# PLL1.net
KiCad netlist of a schematic drawn in Altium Designer
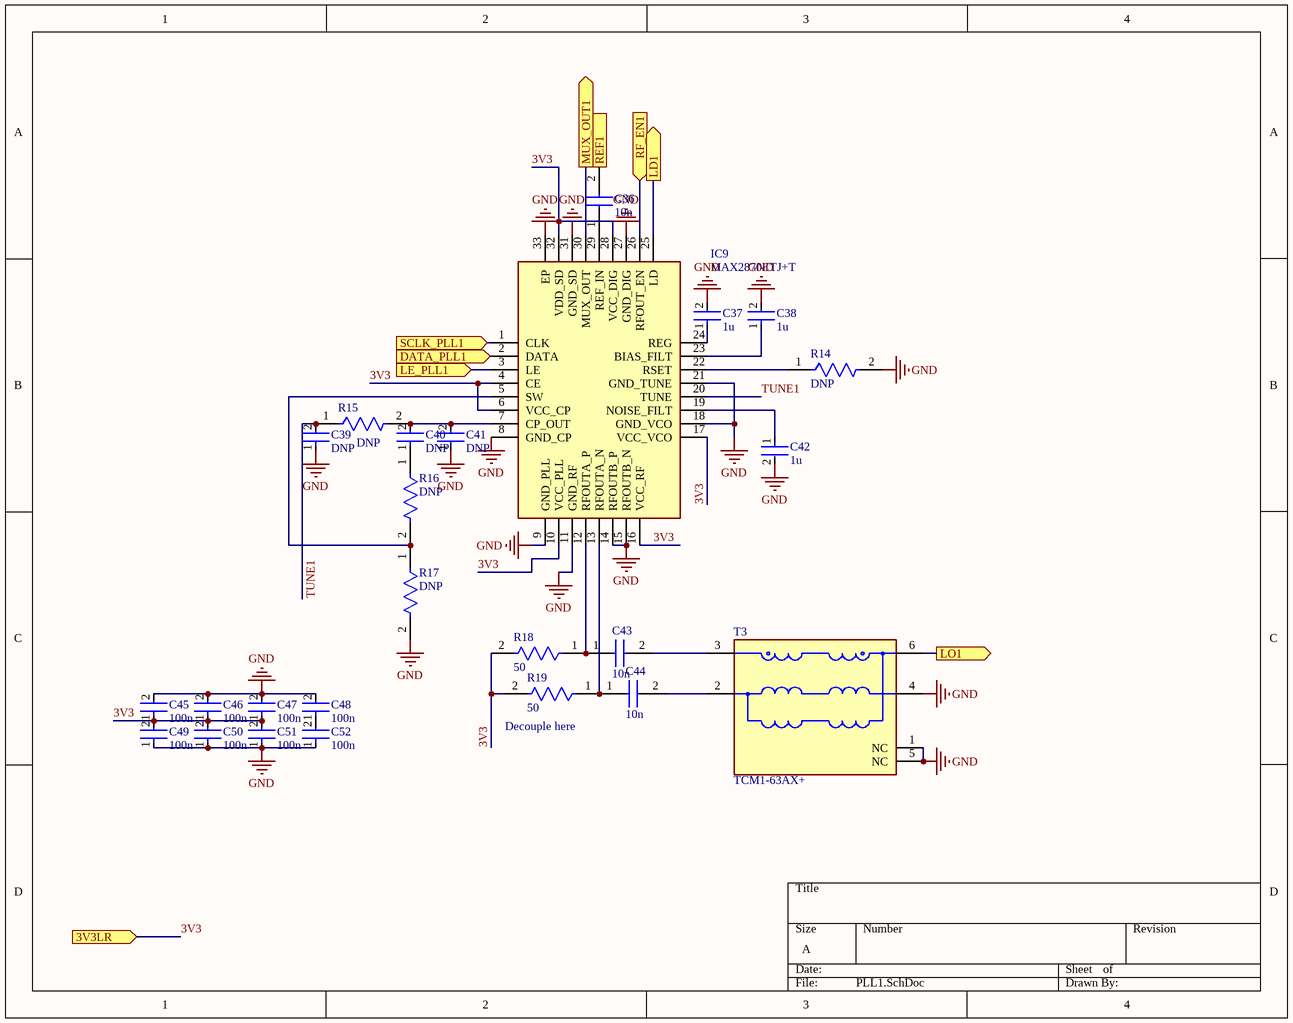
[diagram p0: PLL1.SchDoc]

(export (version "E")
  (design (tool "Eeschema 10.0.6"))
  (components
    (comp (ref "C36")
      (value "10n")
      (footprint "SamacSys:CAPC1005X61N")
      (description "Capacitor")
      (fields
        (field (name "MANUFACTURER_PART_NUMBER") "520L103KT16T")
        (field (name "MOUSER PART NUMBER") "581-520L103KT16T")
      )
      (libsource (lib "*") (part "520L103KT16T"))
    )
    (comp (ref "C37")
      (value "1u")
      (footprint "FP-GRM155-0_1-MFG")
      (description "Chip Multilayer Ceramic Capacitors for General Purpose, 0402, 1.0uF, X5R, 15%, 10%, 50V")
      (libsource (lib "Altium Content Vault") (part "11868f565c42a9108669ba33697ecf6"))
    )
    (comp (ref "C38")
      (value "1u")
      (footprint "FP-GRM155-0_1-MFG")
      (description "Chip Multilayer Ceramic Capacitors for General Purpose, 0402, 1.0uF, X5R, 15%, 10%, 50V")
      (libsource (lib "Altium Content Vault") (part "11868f565c42a9108669ba33697ecf6"))
    )
    (comp (ref "C39")
      (value "DNP")
      (footprint "FP-GRM155-0_05-IPC_C")
      (description "Chip Multilayer Ceramic Capacitors for General Purpose, 0402, 0.10uF, X5R, 15%, 10%, 100V")
      (fields (field (name "TOLERANCE") "10%"))
      (libsource (lib "Altium Content Vault") (part "02cd4be3c70576c341d710602a673aa"))
    )
    (comp (ref "C40")
      (value "DNP")
      (footprint "FP-GRM155-0_05-IPC_C")
      (description "Chip Multilayer Ceramic Capacitors for General Purpose, 0402, 0.10uF, X5R, 15%, 10%, 100V")
      (fields (field (name "TOLERANCE") "10%"))
      (libsource (lib "Altium Content Vault") (part "02cd4be3c70576c341d710602a673aa"))
    )
    (comp (ref "C41")
      (value "DNP")
      (footprint "FP-GRM155-0_05-IPC_C")
      (description "Chip Multilayer Ceramic Capacitors for General Purpose, 0402, 0.10uF, X5R, 15%, 10%, 100V")
      (fields (field (name "TOLERANCE") "10%"))
      (libsource (lib "Altium Content Vault") (part "02cd4be3c70576c341d710602a673aa"))
    )
    (comp (ref "C42")
      (value "1u")
      (footprint "FP-GRM155-0_1-MFG")
      (description "Chip Multilayer Ceramic Capacitors for General Purpose, 0402, 1.0uF, X5R, 15%, 10%, 50V")
      (libsource (lib "Altium Content Vault") (part "11868f565c42a9108669ba33697ecf6"))
    )
    (comp (ref "C43")
      (value "10n")
      (footprint "SamacSys:CAPC1005X61N")
      (description "Capacitor")
      (fields
        (field (name "MANUFACTURER_PART_NUMBER") "520L103KT16T")
        (field (name "MOUSER PART NUMBER") "581-520L103KT16T")
      )
      (libsource (lib "*") (part "520L103KT16T"))
    )
    (comp (ref "C44")
      (value "10n")
      (footprint "SamacSys:CAPC1005X61N")
      (description "Capacitor")
      (fields
        (field (name "MANUFACTURER_PART_NUMBER") "520L103KT16T")
        (field (name "MOUSER PART NUMBER") "581-520L103KT16T")
      )
      (libsource (lib "*") (part "520L103KT16T"))
    )
    (comp (ref "C45")
      (value "100n")
      (footprint "FP-GRM155-0_05-IPC_C")
      (description "Chip Multilayer Ceramic Capacitors for General Purpose, 0402, 0.10uF, X5R, 15%, 10%, 100V")
      (fields (field (name "TOLERANCE") "10%"))
      (libsource (lib "Altium Content Vault") (part "02cd4be3c70576c341d710602a673aa"))
    )
    (comp (ref "C46")
      (value "100n")
      (footprint "FP-GRM155-0_05-IPC_C")
      (description "Chip Multilayer Ceramic Capacitors for General Purpose, 0402, 0.10uF, X5R, 15%, 10%, 100V")
      (fields (field (name "TOLERANCE") "10%"))
      (libsource (lib "Altium Content Vault") (part "02cd4be3c70576c341d710602a673aa"))
    )
    (comp (ref "C47")
      (value "100n")
      (footprint "FP-GRM155-0_05-IPC_C")
      (description "Chip Multilayer Ceramic Capacitors for General Purpose, 0402, 0.10uF, X5R, 15%, 10%, 100V")
      (fields (field (name "TOLERANCE") "10%"))
      (libsource (lib "Altium Content Vault") (part "02cd4be3c70576c341d710602a673aa"))
    )
    (comp (ref "C48")
      (value "100n")
      (footprint "FP-GRM155-0_05-IPC_C")
      (description "Chip Multilayer Ceramic Capacitors for General Purpose, 0402, 0.10uF, X5R, 15%, 10%, 100V")
      (fields (field (name "TOLERANCE") "10%"))
      (libsource (lib "Altium Content Vault") (part "02cd4be3c70576c341d710602a673aa"))
    )
    (comp (ref "C49")
      (value "100n")
      (footprint "FP-GRM155-0_05-IPC_C")
      (description "Chip Multilayer Ceramic Capacitors for General Purpose, 0402, 0.10uF, X5R, 15%, 10%, 100V")
      (fields (field (name "TOLERANCE") "10%"))
      (libsource (lib "Altium Content Vault") (part "02cd4be3c70576c341d710602a673aa"))
    )
    (comp (ref "C50")
      (value "100n")
      (footprint "FP-GRM155-0_05-IPC_C")
      (description "Chip Multilayer Ceramic Capacitors for General Purpose, 0402, 0.10uF, X5R, 15%, 10%, 100V")
      (fields (field (name "TOLERANCE") "10%"))
      (libsource (lib "Altium Content Vault") (part "02cd4be3c70576c341d710602a673aa"))
    )
    (comp (ref "C51")
      (value "100n")
      (footprint "FP-GRM155-0_05-IPC_C")
      (description "Chip Multilayer Ceramic Capacitors for General Purpose, 0402, 0.10uF, X5R, 15%, 10%, 100V")
      (fields (field (name "TOLERANCE") "10%"))
      (libsource (lib "Altium Content Vault") (part "02cd4be3c70576c341d710602a673aa"))
    )
    (comp (ref "C52")
      (value "100n")
      (footprint "FP-GRM155-0_05-IPC_C")
      (description "Chip Multilayer Ceramic Capacitors for General Purpose, 0402, 0.10uF, X5R, 15%, 10%, 100V")
      (fields (field (name "TOLERANCE") "10%"))
      (libsource (lib "Altium Content Vault") (part "02cd4be3c70576c341d710602a673aa"))
    )
    (comp (ref "IC9")
      (value "MAX2870ETJ+T")
      (footprint "SamacSys:QFN50P500X500X80-33N")
      (description "Integrated Circuit")
      (fields (field (name "MOUSER PART NUMBER") "700-MAX2870ETJ+T"))
      (libsource (lib "*") (part "MAX2870ETJ+T"))
    )
    (comp (ref "R14")
      (value "DNP")
      (footprint "FP-AC0402-IPC_B")
      (description "RES 13.3kΩ ±1% 0.063W 0402")
      (fields (field (name "TOLERANCE") "1%"))
      (libsource (lib "Altium Content Vault") (part "1029c3af85768c4190bb7ad29bc67b5"))
    )
    (comp (ref "R15")
      (value "DNP")
      (footprint "FP-AC0402-IPC_B")
      (description "RES 13.3kΩ ±1% 0.063W 0402")
      (fields (field (name "TOLERANCE") "1%"))
      (libsource (lib "Altium Content Vault") (part "1029c3af85768c4190bb7ad29bc67b5"))
    )
    (comp (ref "R16")
      (value "DNP")
      (footprint "FP-AC0402-IPC_B")
      (description "RES 13.3kΩ ±1% 0.063W 0402")
      (fields (field (name "TOLERANCE") "1%"))
      (libsource (lib "Altium Content Vault") (part "1029c3af85768c4190bb7ad29bc67b5"))
    )
    (comp (ref "R17")
      (value "DNP")
      (footprint "FP-AC0402-IPC_B")
      (description "RES 13.3kΩ ±1% 0.063W 0402")
      (fields (field (name "TOLERANCE") "1%"))
      (libsource (lib "Altium Content Vault") (part "1029c3af85768c4190bb7ad29bc67b5"))
    )
    (comp (ref "R18")
      (value "50")
      (footprint "FP-RC0402-0_4-MFG")
      (fields (field (name "TOLERANCE") "5%"))
      (libsource (lib "Altium Content Vault") (part "1029c3af85768c4190bb7ad29bc67b5"))
    )
    (comp (ref "R19")
      (value "50")
      (footprint "FP-RC0402-0_4-MFG")
      (fields (field (name "TOLERANCE") "5%"))
      (libsource (lib "Altium Content Vault") (part "1029c3af85768c4190bb7ad29bc67b5"))
    )
    (comp (ref "T3")
      (value "TCM1-63AX+")
      (footprint "FP-TCM1-63AX+-MFG")
      (description "1:1 CORE & WIRE Transformer, 10 - 6000 MHz, 50Ω")
      (fields
        (field (name "MANUFACTURER") "Mini-Circuits")
        (field (name "OCTOPART") "https://octopart.com/tcm1-63ax%2B-mini-circuits-107315723")
      )
      (libsource (lib "Altium Content Vault") (part "572340aedd709dbafee1a1d3331a406"))
    )
  )
  (nets
    (net (code "1") (name "/3V3") (class "Default")
      (node (ref "C45") (pin "1") (pinfunction "1_1") (pintype "passive"))
      (node (ref "C46") (pin "1") (pinfunction "1_1") (pintype "passive"))
      (node (ref "C47") (pin "1") (pinfunction "1_1") (pintype "passive"))
      (node (ref "C49") (pin "2") (pinfunction "2_2") (pintype "passive"))
      (node (ref "C50") (pin "2") (pinfunction "2_2") (pintype "passive"))
      (node (ref "C51") (pin "2") (pinfunction "2_2") (pintype "passive"))
      (node (ref "IC9") (pin "10") (pinfunction "VCC_PLL_10") (pintype "passive"))
      (node (ref "IC9") (pin "16") (pinfunction "VCC_RF_16") (pintype "passive"))
      (node (ref "IC9") (pin "17") (pinfunction "VCC_VCO_17") (pintype "passive"))
      (node (ref "IC9") (pin "28") (pinfunction "VCC_DIG_28") (pintype "passive"))
      (node (ref "IC9") (pin "32") (pinfunction "VDD_SD_32") (pintype "passive"))
      (node (ref "IC9") (pin "4") (pinfunction "CE_4") (pintype "passive"))
      (node (ref "IC9") (pin "6") (pinfunction "VCC_CP_6") (pintype "passive"))
      (node (ref "R18") (pin "2") (pinfunction "2_2") (pintype "passive"))
      (node (ref "R19") (pin "2") (pinfunction "2_2") (pintype "passive"))
    )
    (net (code "2") (name "/DATA_PLL1") (class "Default")
      (node (ref "IC9") (pin "2") (pinfunction "DATA_2") (pintype "passive"))
    )
    (net (code "3") (name "/LD1") (class "Default")
      (node (ref "IC9") (pin "25") (pinfunction "LD_25") (pintype "passive"))
    )
    (net (code "4") (name "/LE_PLL1") (class "Default")
      (node (ref "IC9") (pin "3") (pinfunction "LE_3") (pintype "passive"))
    )
    (net (code "5") (name "/LO1") (class "Default")
      (node (ref "T3") (pin "6") (pinfunction "SECONDARY_DOT_6") (pintype "passive"))
    )
    (net (code "6") (name "/MUX_OUT1") (class "Default")
      (node (ref "IC9") (pin "30") (pinfunction "MUX_OUT_30") (pintype "passive"))
    )
    (net (code "7") (name "/REF1") (class "Default")
      (node (ref "C36") (pin "2") (pinfunction "2_2") (pintype "passive"))
    )
    (net (code "8") (name "/RF_EN1") (class "Default")
      (node (ref "IC9") (pin "26") (pinfunction "RFOUT_EN_26") (pintype "passive"))
    )
    (net (code "9") (name "/SCLK_PLL1") (class "Default")
      (node (ref "IC9") (pin "1") (pinfunction "CLK_1") (pintype "passive"))
    )
    (net (code "10") (name "/TUNE1") (class "Default")
      (node (ref "C39") (pin "2") (pinfunction "2_2") (pintype "passive"))
      (node (ref "IC9") (pin "20") (pinfunction "TUNE_20") (pintype "passive"))
      (node (ref "R15") (pin "1") (pinfunction "1_1") (pintype "passive"))
    )
    (net (code "11") (name "GND") (class "Default")
      (node (ref "C37") (pin "2") (pinfunction "2_2") (pintype "passive"))
      (node (ref "C38") (pin "2") (pinfunction "2_2") (pintype "passive"))
      (node (ref "C39") (pin "1") (pinfunction "1_1") (pintype "passive"))
      (node (ref "C41") (pin "1") (pinfunction "1_1") (pintype "passive"))
      (node (ref "C42") (pin "2") (pinfunction "2_2") (pintype "passive"))
      (node (ref "C45") (pin "2") (pinfunction "2_2") (pintype "passive"))
      (node (ref "C46") (pin "2") (pinfunction "2_2") (pintype "passive"))
      (node (ref "C47") (pin "2") (pinfunction "2_2") (pintype "passive"))
      (node (ref "C48") (pin "2") (pinfunction "2_2") (pintype "passive"))
      (node (ref "C49") (pin "1") (pinfunction "1_1") (pintype "passive"))
      (node (ref "C50") (pin "1") (pinfunction "1_1") (pintype "passive"))
      (node (ref "C51") (pin "1") (pinfunction "1_1") (pintype "passive"))
      (node (ref "C52") (pin "1") (pinfunction "1_1") (pintype "passive"))
      (node (ref "IC9") (pin "11") (pinfunction "GND_RF_11") (pintype "passive"))
      (node (ref "IC9") (pin "14") (pinfunction "RFOUTB_P_14") (pintype "passive"))
      (node (ref "IC9") (pin "15") (pinfunction "RFOUTB_N_15") (pintype "passive"))
      (node (ref "IC9") (pin "18") (pinfunction "GND_VCO_18") (pintype "passive"))
      (node (ref "IC9") (pin "21") (pinfunction "GND_TUNE_21") (pintype "passive"))
      (node (ref "IC9") (pin "27") (pinfunction "GND_DIG_27") (pintype "passive"))
      (node (ref "IC9") (pin "31") (pinfunction "GND_SD_31") (pintype "passive"))
      (node (ref "IC9") (pin "33") (pinfunction "EP_33") (pintype "passive"))
      (node (ref "IC9") (pin "8") (pinfunction "GND_CP_8") (pintype "passive"))
      (node (ref "IC9") (pin "9") (pinfunction "GND_PLL_9") (pintype "passive"))
      (node (ref "R14") (pin "2") (pinfunction "2_2") (pintype "passive"))
      (node (ref "R17") (pin "2") (pinfunction "2_2") (pintype "passive"))
      (node (ref "T3") (pin "1") (pinfunction "NC_1") (pintype "passive"))
      (node (ref "T3") (pin "4") (pinfunction "SECONDARY_4") (pintype "passive"))
      (node (ref "T3") (pin "5") (pinfunction "NC_5") (pintype "passive"))
    )
    (net (code "12") (name "Net-(C40-Pad1)") (class "Default")
      (node (ref "C40") (pin "1") (pinfunction "1_1") (pintype "passive"))
      (node (ref "R16") (pin "1") (pinfunction "1_1") (pintype "passive"))
    )
    (net (code "13") (name "Net-(C48-Pad1)") (class "Default")
      (node (ref "C48") (pin "1") (pinfunction "1_1") (pintype "passive"))
      (node (ref "C52") (pin "2") (pinfunction "2_2") (pintype "passive"))
    )
    (net (code "14") (name "Net-(IC9-BIAS_FILT)") (class "Default")
      (node (ref "C38") (pin "1") (pinfunction "1_1") (pintype "passive"))
      (node (ref "IC9") (pin "23") (pinfunction "BIAS_FILT_23") (pintype "passive"))
    )
    (net (code "15") (name "Net-(IC9-CP_OUT)") (class "Default")
      (node (ref "C40") (pin "2") (pinfunction "2_2") (pintype "passive"))
      (node (ref "C41") (pin "2") (pinfunction "2_2") (pintype "passive"))
      (node (ref "IC9") (pin "7") (pinfunction "CP_OUT_7") (pintype "passive"))
      (node (ref "R15") (pin "2") (pinfunction "2_2") (pintype "passive"))
    )
    (net (code "16") (name "Net-(IC9-NOISE_FILT)") (class "Default")
      (node (ref "C42") (pin "1") (pinfunction "1_1") (pintype "passive"))
      (node (ref "IC9") (pin "19") (pinfunction "NOISE_FILT_19") (pintype "passive"))
    )
    (net (code "17") (name "Net-(IC9-REF_IN)") (class "Default")
      (node (ref "C36") (pin "1") (pinfunction "1_1") (pintype "passive"))
      (node (ref "IC9") (pin "29") (pinfunction "REF_IN_29") (pintype "passive"))
    )
    (net (code "18") (name "Net-(IC9-REG)") (class "Default")
      (node (ref "C37") (pin "1") (pinfunction "1_1") (pintype "passive"))
      (node (ref "IC9") (pin "24") (pinfunction "REG_24") (pintype "passive"))
    )
    (net (code "19") (name "Net-(IC9-RFOUTA_N)") (class "Default")
      (node (ref "C44") (pin "1") (pinfunction "1_1") (pintype "passive"))
      (node (ref "IC9") (pin "13") (pinfunction "RFOUTA_N_13") (pintype "passive"))
      (node (ref "R19") (pin "1") (pinfunction "1_1") (pintype "passive"))
    )
    (net (code "20") (name "Net-(IC9-RFOUTA_P)") (class "Default")
      (node (ref "C43") (pin "1") (pinfunction "1_1") (pintype "passive"))
      (node (ref "IC9") (pin "12") (pinfunction "RFOUTA_P_12") (pintype "passive"))
      (node (ref "R18") (pin "1") (pinfunction "1_1") (pintype "passive"))
    )
    (net (code "21") (name "Net-(IC9-RSET)") (class "Default")
      (node (ref "IC9") (pin "22") (pinfunction "RSET_22") (pintype "passive"))
      (node (ref "R14") (pin "1") (pinfunction "1_1") (pintype "passive"))
    )
    (net (code "22") (name "Net-(IC9-SW)") (class "Default")
      (node (ref "IC9") (pin "5") (pinfunction "SW_5") (pintype "passive"))
      (node (ref "R16") (pin "2") (pinfunction "2_2") (pintype "passive"))
      (node (ref "R17") (pin "1") (pinfunction "1_1") (pintype "passive"))
    )
    (net (code "23") (name "Net-(T3-GND)") (class "Default")
      (node (ref "C44") (pin "2") (pinfunction "2_2") (pintype "passive"))
      (node (ref "T3") (pin "2") (pinfunction "GND_2") (pintype "passive"))
    )
    (net (code "24") (name "Net-(T3-PRIMARY_DOT)") (class "Default")
      (node (ref "C43") (pin "2") (pinfunction "2_2") (pintype "passive"))
      (node (ref "T3") (pin "3") (pinfunction "PRIMARY_DOT_3") (pintype "passive"))
    )
  )
)
